# Ultrasonic_Distance_Measurment_Schematic.net
KiCad netlist of a schematic drawn in EasyEDA
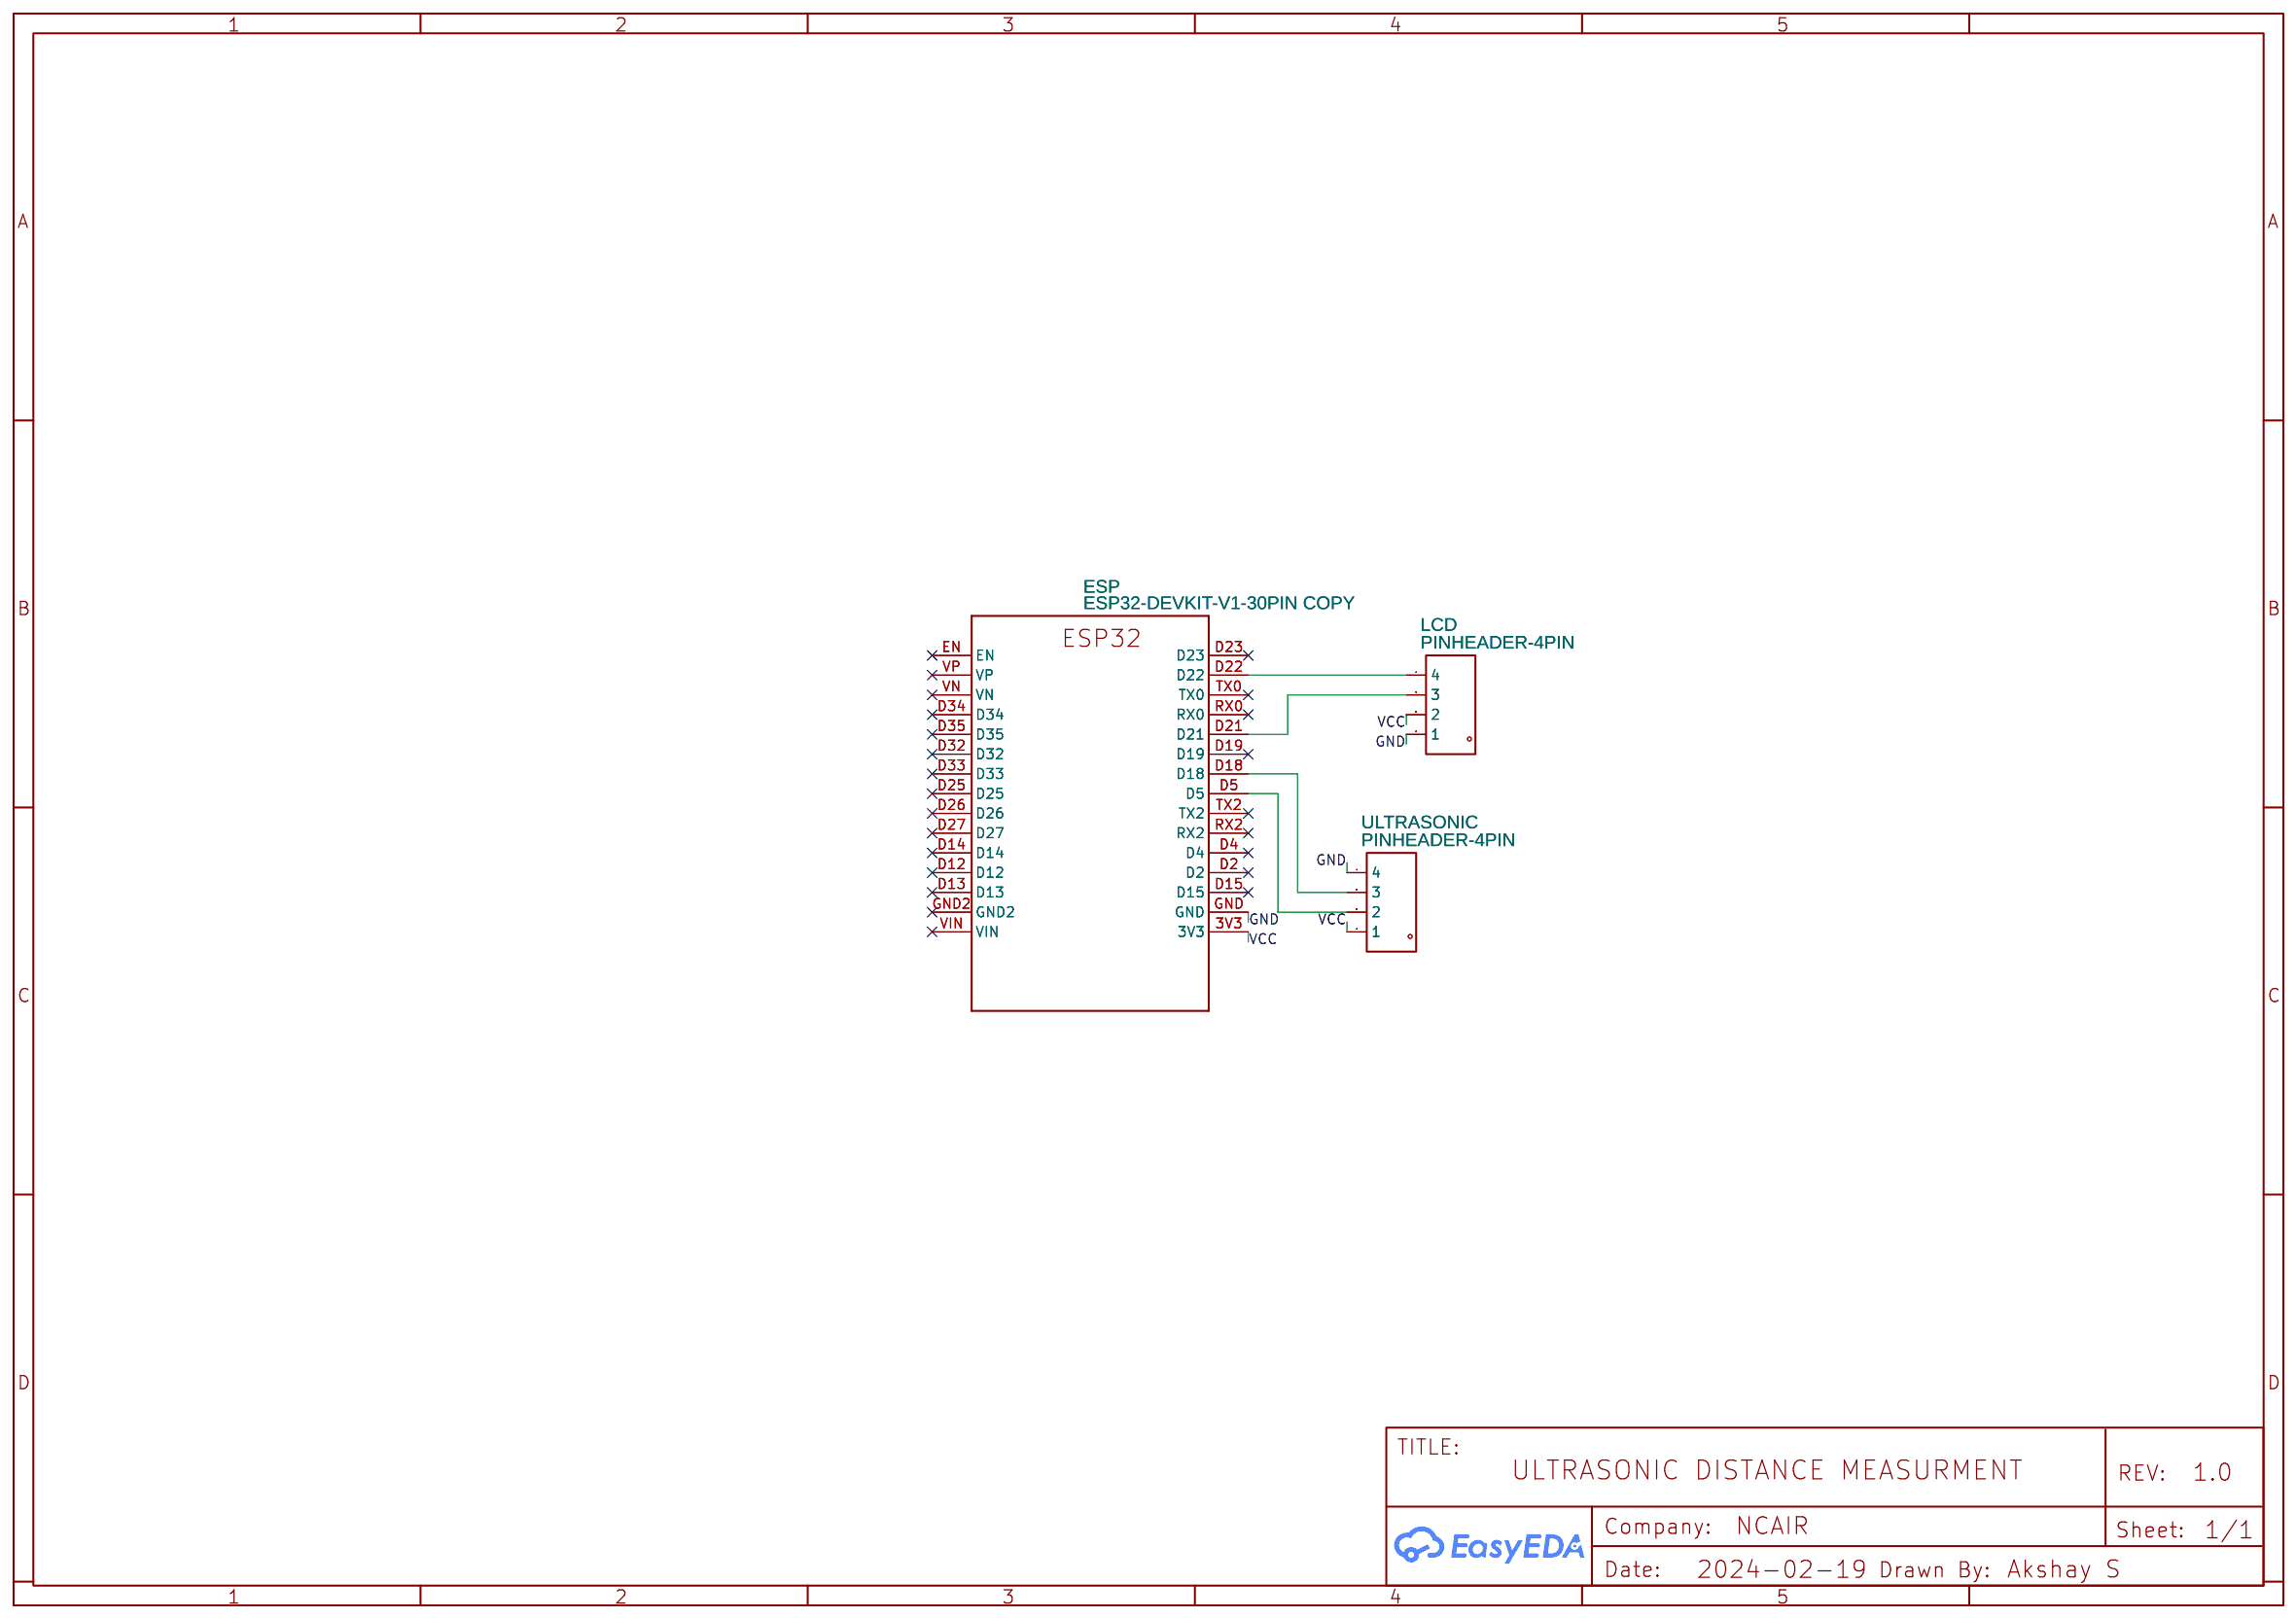
[diagram p0: schematic sheet]

(export (version "E")
  (design (tool "Eeschema 10.0.6"))
  (components
    (comp (ref "ESP")
      (value "ESP32-DEVKIT-V1-30PIN COPY")
      (libsource (lib "") (part "ESP32-DEVKIT-V1-30PIN"))
    )
    (comp (ref "LCD") (value "PINHEADER-4PIN") (libsource (lib "") (part "PINHEADER-4PIN")))
    (comp (ref "ULTRASONIC") (value "PINHEADER-4PIN") (libsource (lib "") (part "PINHEADER-4PIN_1")))
  )
  (nets
    (net (code "1") (name "/GND") (class "Default")
      (node (ref "ESP") (pin "GND") (pinfunction "GND_GND") (pintype "unspecified"))
      (node (ref "LCD") (pin "1") (pinfunction "1_1") (pintype "input"))
      (node (ref "ULTRASONIC") (pin "4") (pinfunction "4_4") (pintype "input"))
    )
    (net (code "2") (name "/VCC") (class "Default")
      (node (ref "ESP") (pin "3V3") (pinfunction "3V3_3V3") (pintype "unspecified"))
      (node (ref "LCD") (pin "2") (pinfunction "2_2") (pintype "input"))
      (node (ref "ULTRASONIC") (pin "1") (pinfunction "1_1") (pintype "input"))
    )
    (net (code "3") (name "Net-(ESP-PadD5)") (class "Default")
      (node (ref "ESP") (pin "D5") (pinfunction "D5_D5") (pintype "unspecified"))
      (node (ref "ULTRASONIC") (pin "2") (pinfunction "2_2") (pintype "input"))
    )
    (net (code "4") (name "Net-(ESP-PadD18)") (class "Default")
      (node (ref "ESP") (pin "D18") (pinfunction "D18_D18") (pintype "unspecified"))
      (node (ref "ULTRASONIC") (pin "3") (pinfunction "3_3") (pintype "input"))
    )
    (net (code "5") (name "Net-(ESP-PadD21)") (class "Default")
      (node (ref "ESP") (pin "D21") (pinfunction "D21_D21") (pintype "unspecified"))
      (node (ref "LCD") (pin "3") (pinfunction "3_3") (pintype "input"))
    )
    (net (code "6") (name "Net-(ESP-PadD22)") (class "Default")
      (node (ref "ESP") (pin "D22") (pinfunction "D22_D22") (pintype "unspecified"))
      (node (ref "LCD") (pin "4") (pinfunction "4_4") (pintype "input"))
    )
    (net (code "7") (name "unconnected-(ESP-PadD2)") (class "Default")
      (node (ref "ESP") (pin "D2") (pinfunction "D2_D2") (pintype "unspecified+no_connect"))
    )
    (net (code "8") (name "unconnected-(ESP-PadD4)") (class "Default")
      (node (ref "ESP") (pin "D4") (pinfunction "D4_D4") (pintype "unspecified+no_connect"))
    )
    (net (code "9") (name "unconnected-(ESP-PadD12)") (class "Default")
      (node (ref "ESP") (pin "D12") (pinfunction "D12_D12") (pintype "unspecified+no_connect"))
    )
    (net (code "10") (name "unconnected-(ESP-PadD13)") (class "Default")
      (node (ref "ESP") (pin "D13") (pinfunction "D13_D13") (pintype "unspecified+no_connect"))
    )
    (net (code "11") (name "unconnected-(ESP-PadD14)") (class "Default")
      (node (ref "ESP") (pin "D14") (pinfunction "D14_D14") (pintype "unspecified+no_connect"))
    )
    (net (code "12") (name "unconnected-(ESP-PadD15)") (class "Default")
      (node (ref "ESP") (pin "D15") (pinfunction "D15_D15") (pintype "unspecified+no_connect"))
    )
    (net (code "13") (name "unconnected-(ESP-PadD19)") (class "Default")
      (node (ref "ESP") (pin "D19") (pinfunction "D19_D19") (pintype "unspecified+no_connect"))
    )
    (net (code "14") (name "unconnected-(ESP-PadD23)") (class "Default")
      (node (ref "ESP") (pin "D23") (pinfunction "D23_D23") (pintype "unspecified+no_connect"))
    )
    (net (code "15") (name "unconnected-(ESP-PadD25)") (class "Default")
      (node (ref "ESP") (pin "D25") (pinfunction "D25_D25") (pintype "unspecified+no_connect"))
    )
    (net (code "16") (name "unconnected-(ESP-PadD26)") (class "Default")
      (node (ref "ESP") (pin "D26") (pinfunction "D26_D26") (pintype "unspecified+no_connect"))
    )
    (net (code "17") (name "unconnected-(ESP-PadD27)") (class "Default")
      (node (ref "ESP") (pin "D27") (pinfunction "D27_D27") (pintype "unspecified+no_connect"))
    )
    (net (code "18") (name "unconnected-(ESP-PadD32)") (class "Default")
      (node (ref "ESP") (pin "D32") (pinfunction "D32_D32") (pintype "unspecified+no_connect"))
    )
    (net (code "19") (name "unconnected-(ESP-PadD33)") (class "Default")
      (node (ref "ESP") (pin "D33") (pinfunction "D33_D33") (pintype "unspecified+no_connect"))
    )
    (net (code "20") (name "unconnected-(ESP-PadD34)") (class "Default")
      (node (ref "ESP") (pin "D34") (pinfunction "D34_D34") (pintype "unspecified+no_connect"))
    )
    (net (code "21") (name "unconnected-(ESP-PadD35)") (class "Default")
      (node (ref "ESP") (pin "D35") (pinfunction "D35_D35") (pintype "unspecified+no_connect"))
    )
    (net (code "22") (name "unconnected-(ESP-PadEN)") (class "Default")
      (node (ref "ESP") (pin "EN") (pinfunction "EN_EN") (pintype "unspecified+no_connect"))
    )
    (net (code "23") (name "unconnected-(ESP-PadGND2)") (class "Default")
      (node (ref "ESP") (pin "GND2") (pinfunction "GND2_GND2") (pintype "unspecified+no_connect"))
    )
    (net (code "24") (name "unconnected-(ESP-PadRX0)") (class "Default")
      (node (ref "ESP") (pin "RX0") (pinfunction "RX0_RX0") (pintype "unspecified+no_connect"))
    )
    (net (code "25") (name "unconnected-(ESP-PadRX2)") (class "Default")
      (node (ref "ESP") (pin "RX2") (pinfunction "RX2_RX2") (pintype "unspecified+no_connect"))
    )
    (net (code "26") (name "unconnected-(ESP-PadTX0)") (class "Default")
      (node (ref "ESP") (pin "TX0") (pinfunction "TX0_TX0") (pintype "unspecified+no_connect"))
    )
    (net (code "27") (name "unconnected-(ESP-PadTX2)") (class "Default")
      (node (ref "ESP") (pin "TX2") (pinfunction "TX2_TX2") (pintype "unspecified+no_connect"))
    )
    (net (code "28") (name "unconnected-(ESP-PadVIN)") (class "Default")
      (node (ref "ESP") (pin "VIN") (pinfunction "VIN_VIN") (pintype "unspecified+no_connect"))
    )
    (net (code "29") (name "unconnected-(ESP-PadVN)") (class "Default")
      (node (ref "ESP") (pin "VN") (pinfunction "VN_VN") (pintype "unspecified+no_connect"))
    )
    (net (code "30") (name "unconnected-(ESP-PadVP)") (class "Default")
      (node (ref "ESP") (pin "VP") (pinfunction "VP_VP") (pintype "unspecified+no_connect"))
    )
  )
)
